# RF_PA.net
KiCad netlist of a schematic drawn in EAGLE
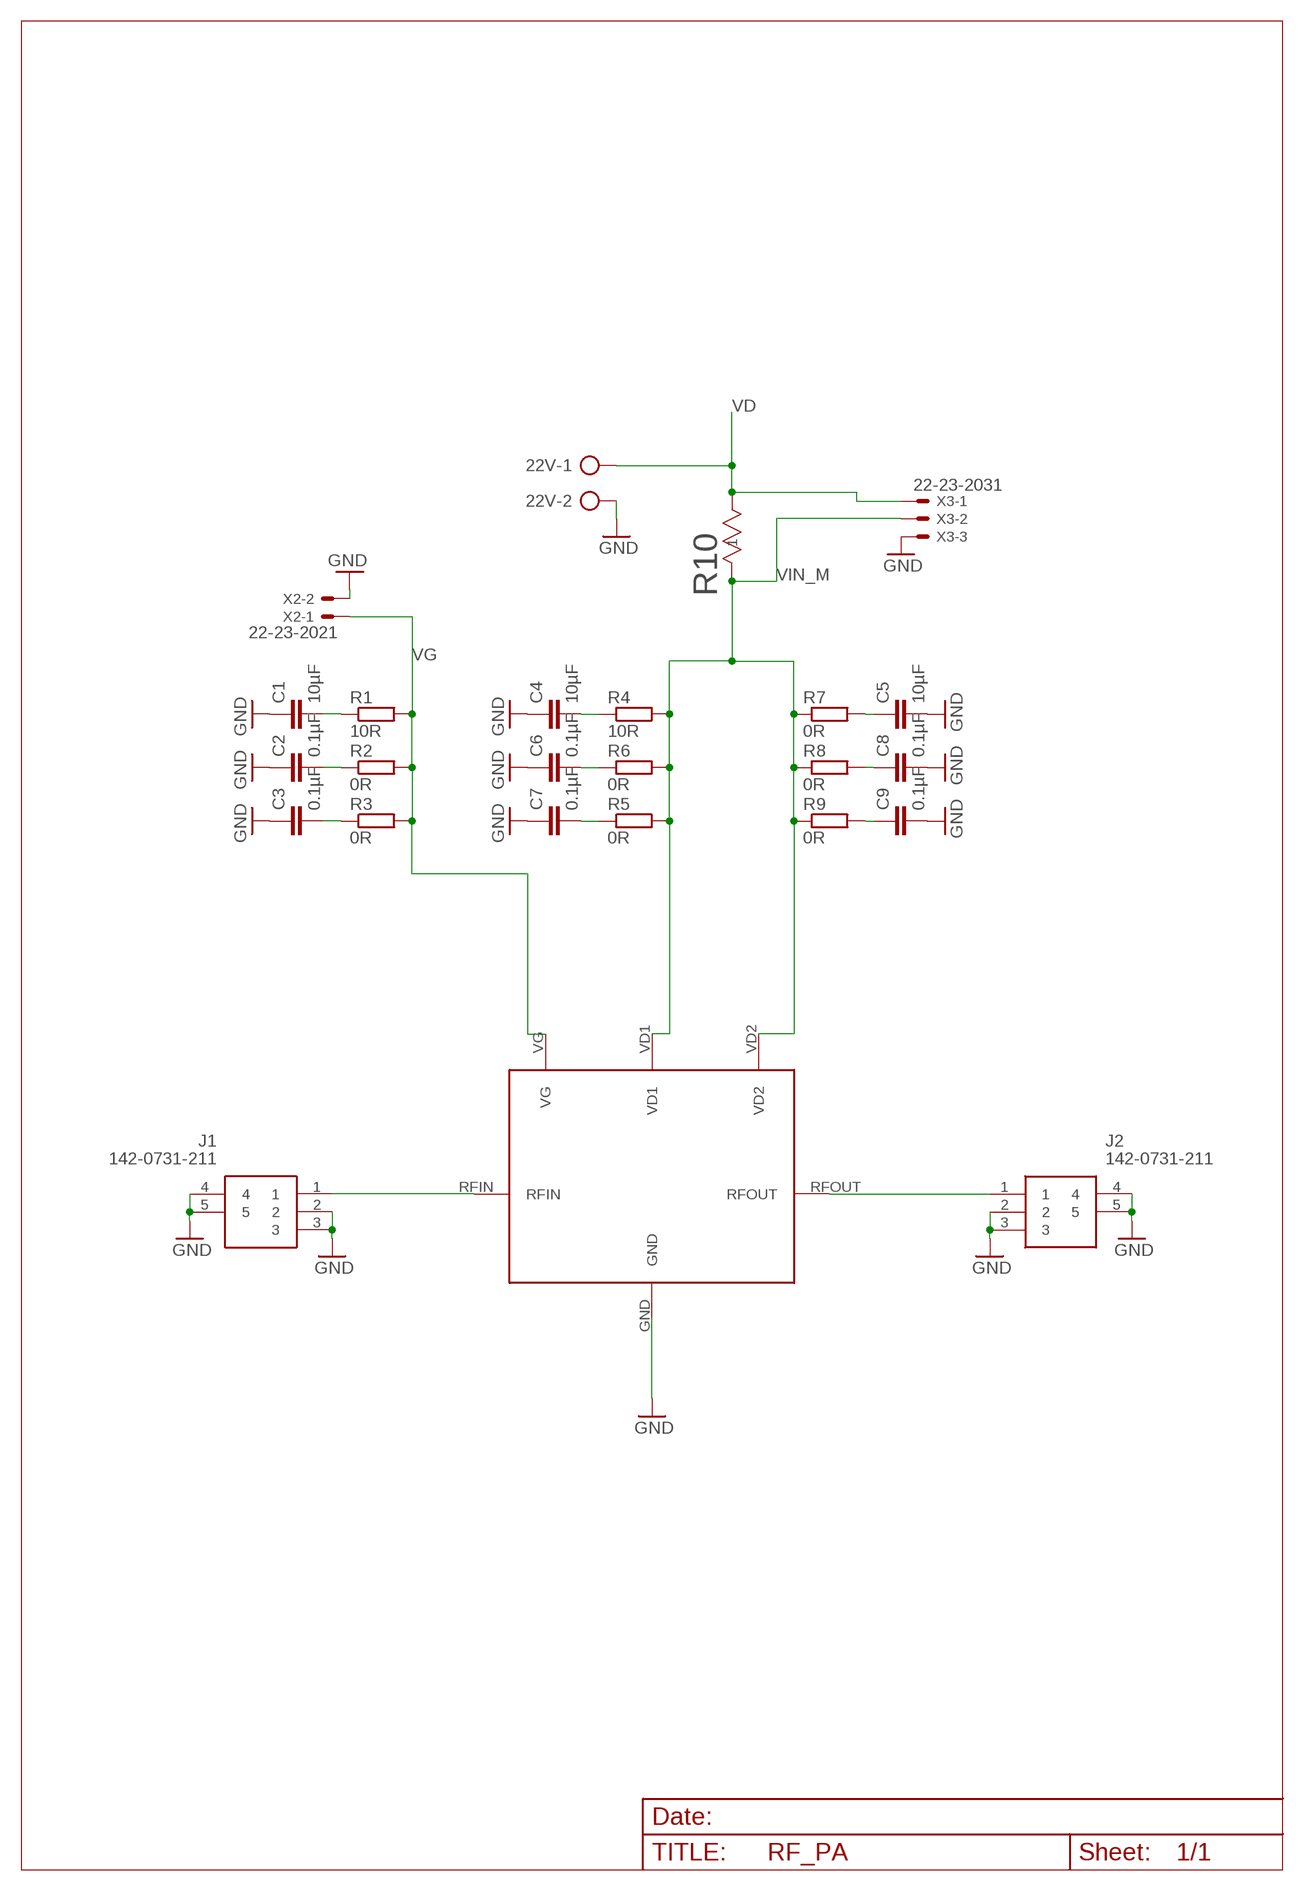
[diagram p0: schematic, sheet 1]

(export (version "E")
  (design (tool "Eeschema 10.0.6"))
  (components
    (comp (ref "22V")
      (value "AK300/2")
      (footprint "eagle-import:AK300_2")
      (libsource (lib "eagle-import") (part "AK300/2"))
    )
    (comp (ref "C1")
      (value "10µF")
      (footprint "eagle-import:C1206")
      (libsource (lib "eagle-import") (part "C-EUC1206"))
    )
    (comp (ref "C2")
      (value "0.1µF")
      (footprint "eagle-import:C0402")
      (libsource (lib "eagle-import") (part "C-EUC0402"))
    )
    (comp (ref "C3")
      (value "0.1µF")
      (footprint "eagle-import:C0402")
      (libsource (lib "eagle-import") (part "C-EUC0402"))
    )
    (comp (ref "C4")
      (value "10µF")
      (footprint "eagle-import:C1206")
      (libsource (lib "eagle-import") (part "C-EUC1206"))
    )
    (comp (ref "C5")
      (value "10µF")
      (footprint "eagle-import:C1206")
      (libsource (lib "eagle-import") (part "C-EUC1206"))
    )
    (comp (ref "C6")
      (value "0.1µF")
      (footprint "eagle-import:C0402")
      (libsource (lib "eagle-import") (part "C-EUC0402"))
    )
    (comp (ref "C7")
      (value "0.1µF")
      (footprint "eagle-import:C0402")
      (libsource (lib "eagle-import") (part "C-EUC0402"))
    )
    (comp (ref "C8")
      (value "0.1µF")
      (footprint "eagle-import:C0402")
      (libsource (lib "eagle-import") (part "C-EUC0402"))
    )
    (comp (ref "C9")
      (value "0.1µF")
      (footprint "eagle-import:C0402")
      (libsource (lib "eagle-import") (part "C-EUC0402"))
    )
    (comp (ref "J1")
      (value "142-0731-211")
      (footprint "eagle-import:1420731211")
      (fields (field (name "MOUSER_PART_NUMBER") "530-142-0731-211"))
      (libsource (lib "eagle-import") (part "142-0731-211"))
    )
    (comp (ref "J2")
      (value "142-0731-211")
      (footprint "eagle-import:1420731211")
      (fields (field (name "MOUSER_PART_NUMBER") "530-142-0731-211"))
      (libsource (lib "eagle-import") (part "142-0731-211"))
    )
    (comp (ref "R1")
      (value "10R")
      (footprint "eagle-import:R0402")
      (libsource (lib "eagle-import") (part "R-EU_R0402"))
    )
    (comp (ref "R2")
      (value "0R")
      (footprint "eagle-import:R0402")
      (libsource (lib "eagle-import") (part "R-EU_R0402"))
    )
    (comp (ref "R3")
      (value "0R")
      (footprint "eagle-import:R0402")
      (libsource (lib "eagle-import") (part "R-EU_R0402"))
    )
    (comp (ref "R4")
      (value "10R")
      (footprint "eagle-import:R0402")
      (libsource (lib "eagle-import") (part "R-EU_R0402"))
    )
    (comp (ref "R5")
      (value "0R")
      (footprint "eagle-import:R0402")
      (libsource (lib "eagle-import") (part "R-EU_R0402"))
    )
    (comp (ref "R6")
      (value "0R")
      (footprint "eagle-import:R0603")
      (libsource (lib "eagle-import") (part "R-EU_R0603"))
    )
    (comp (ref "R7")
      (value "0R")
      (footprint "eagle-import:R0402")
      (libsource (lib "eagle-import") (part "R-EU_R0402"))
    )
    (comp (ref "R8")
      (value "0R")
      (footprint "eagle-import:R0402")
      (libsource (lib "eagle-import") (part "R-EU_R0402"))
    )
    (comp (ref "R9")
      (value "0R")
      (footprint "eagle-import:R0402")
      (libsource (lib "eagle-import") (part "R-EU_R0402"))
    )
    (comp (ref "R10")
      (value "5mR")
      (footprint "eagle-import:WSL2816_VIS")
      (fields
        (field (name "MANUFACTURER_PART_NUMBER") "WSL2816R1000FEH")
        (field (name "COPYRIGHT") "Copyright (C) 2025 Ultra Librarian. All rights reserved.")
      )
      (libsource (lib "eagle-import") (part "WSL2816R1000FEH"))
    )
    (comp (ref "U$1")
      (value "QPA2962_B")
      (footprint "eagle-import:QPA2962_B")
      (libsource (lib "eagle-import") (part "QPA2962_B"))
    )
    (comp (ref "X2")
      (value "22-23-2021")
      (footprint "eagle-import:22-23-2021")
      (fields (field (name "MF") "MOLEX"))
      (libsource (lib "eagle-import") (part "22-23-2021"))
    )
    (comp (ref "X3")
      (value "22-23-2031")
      (footprint "eagle-import:22-23-2031")
      (fields (field (name "MF") "MOLEX"))
      (libsource (lib "eagle-import") (part "22-23-2031"))
    )
  )
  (nets
    (net (code "1") (name "/VD") (class "Default")
      (node (ref "22V") (pin "1") (pinfunction "KL_1") (pintype "passive"))
      (node (ref "R10") (pin "2") (pinfunction "2_2") (pintype "passive"))
      (node (ref "X3") (pin "1") (pinfunction "S_1") (pintype "passive"))
    )
    (net (code "2") (name "/VG") (class "Default")
      (node (ref "R1") (pin "2") (pinfunction "2_2") (pintype "passive"))
      (node (ref "R2") (pin "2") (pinfunction "2_2") (pintype "passive"))
      (node (ref "R3") (pin "2") (pinfunction "2_2") (pintype "passive"))
      (node (ref "U$1") (pin "VG") (pinfunction "VG_VG") (pintype "bidirectional"))
      (node (ref "X2") (pin "1") (pinfunction "S_1") (pintype "passive"))
    )
    (net (code "3") (name "/VIN_M") (class "Default")
      (node (ref "R10") (pin "1") (pinfunction "1_1") (pintype "passive"))
      (node (ref "R4") (pin "2") (pinfunction "2_2") (pintype "passive"))
      (node (ref "R5") (pin "2") (pinfunction "2_2") (pintype "passive"))
      (node (ref "R6") (pin "2") (pinfunction "2_2") (pintype "passive"))
      (node (ref "R7") (pin "1") (pinfunction "1_1") (pintype "passive"))
      (node (ref "R8") (pin "1") (pinfunction "1_1") (pintype "passive"))
      (node (ref "R9") (pin "1") (pinfunction "1_1") (pintype "passive"))
      (node (ref "U$1") (pin "VD1") (pinfunction "VD1_VD1") (pintype "bidirectional"))
      (node (ref "U$1") (pin "VD2") (pinfunction "VD2_VD2") (pintype "bidirectional"))
      (node (ref "X3") (pin "2") (pinfunction "S_2") (pintype "passive"))
    )
    (net (code "4") (name "GND") (class "Default")
      (node (ref "22V") (pin "2") (pinfunction "KL_2") (pintype "passive"))
      (node (ref "C1") (pin "1") (pinfunction "1_1") (pintype "passive"))
      (node (ref "C2") (pin "1") (pinfunction "1_1") (pintype "passive"))
      (node (ref "C3") (pin "1") (pinfunction "1_1") (pintype "passive"))
      (node (ref "C4") (pin "1") (pinfunction "1_1") (pintype "passive"))
      (node (ref "C5") (pin "2") (pinfunction "2_2") (pintype "passive"))
      (node (ref "C6") (pin "1") (pinfunction "1_1") (pintype "passive"))
      (node (ref "C7") (pin "1") (pinfunction "1_1") (pintype "passive"))
      (node (ref "C8") (pin "2") (pinfunction "2_2") (pintype "passive"))
      (node (ref "C9") (pin "2") (pinfunction "2_2") (pintype "passive"))
      (node (ref "J1") (pin "2") (pinfunction "2_2") (pintype "bidirectional"))
      (node (ref "J1") (pin "3") (pinfunction "3_3") (pintype "bidirectional"))
      (node (ref "J1") (pin "4") (pinfunction "4_4") (pintype "bidirectional"))
      (node (ref "J1") (pin "5") (pinfunction "5_5") (pintype "bidirectional"))
      (node (ref "J2") (pin "2") (pinfunction "2_2") (pintype "bidirectional"))
      (node (ref "J2") (pin "3") (pinfunction "3_3") (pintype "bidirectional"))
      (node (ref "J2") (pin "4") (pinfunction "4_4") (pintype "bidirectional"))
      (node (ref "J2") (pin "5") (pinfunction "5_5") (pintype "bidirectional"))
      (node (ref "U$1") (pin "GND") (pinfunction "GND_GND") (pintype "bidirectional"))
      (node (ref "X2") (pin "2") (pinfunction "S_2") (pintype "passive"))
      (node (ref "X3") (pin "3") (pinfunction "S_3") (pintype "passive"))
    )
    (net (code "5") (name "Net-(C1-Pad2)") (class "Default")
      (node (ref "C1") (pin "2") (pinfunction "2_2") (pintype "passive"))
      (node (ref "R1") (pin "1") (pinfunction "1_1") (pintype "passive"))
    )
    (net (code "6") (name "Net-(C2-Pad2)") (class "Default")
      (node (ref "C2") (pin "2") (pinfunction "2_2") (pintype "passive"))
      (node (ref "R2") (pin "1") (pinfunction "1_1") (pintype "passive"))
    )
    (net (code "7") (name "Net-(C3-Pad2)") (class "Default")
      (node (ref "C3") (pin "2") (pinfunction "2_2") (pintype "passive"))
      (node (ref "R3") (pin "1") (pinfunction "1_1") (pintype "passive"))
    )
    (net (code "8") (name "Net-(C4-Pad2)") (class "Default")
      (node (ref "C4") (pin "2") (pinfunction "2_2") (pintype "passive"))
      (node (ref "R4") (pin "1") (pinfunction "1_1") (pintype "passive"))
    )
    (net (code "9") (name "Net-(C5-Pad1)") (class "Default")
      (node (ref "C5") (pin "1") (pinfunction "1_1") (pintype "passive"))
      (node (ref "R7") (pin "2") (pinfunction "2_2") (pintype "passive"))
    )
    (net (code "10") (name "Net-(C6-Pad2)") (class "Default")
      (node (ref "C6") (pin "2") (pinfunction "2_2") (pintype "passive"))
      (node (ref "R6") (pin "1") (pinfunction "1_1") (pintype "passive"))
    )
    (net (code "11") (name "Net-(C7-Pad2)") (class "Default")
      (node (ref "C7") (pin "2") (pinfunction "2_2") (pintype "passive"))
      (node (ref "R5") (pin "1") (pinfunction "1_1") (pintype "passive"))
    )
    (net (code "12") (name "Net-(C8-Pad1)") (class "Default")
      (node (ref "C8") (pin "1") (pinfunction "1_1") (pintype "passive"))
      (node (ref "R8") (pin "2") (pinfunction "2_2") (pintype "passive"))
    )
    (net (code "13") (name "Net-(C9-Pad1)") (class "Default")
      (node (ref "C9") (pin "1") (pinfunction "1_1") (pintype "passive"))
      (node (ref "R9") (pin "2") (pinfunction "2_2") (pintype "passive"))
    )
    (net (code "14") (name "Net-(J1-Pad1)") (class "Default")
      (node (ref "J1") (pin "1") (pinfunction "1_1") (pintype "bidirectional"))
      (node (ref "U$1") (pin "RFIN") (pinfunction "RFIN_RFIN") (pintype "bidirectional"))
    )
    (net (code "15") (name "Net-(J2-Pad1)") (class "Default")
      (node (ref "J2") (pin "1") (pinfunction "1_1") (pintype "bidirectional"))
      (node (ref "U$1") (pin "RFOUT") (pinfunction "RFOUT_RFOUT") (pintype "bidirectional"))
    )
  )
)
